# HC05_shield.net
KiCad netlist of a schematic drawn in EAGLE
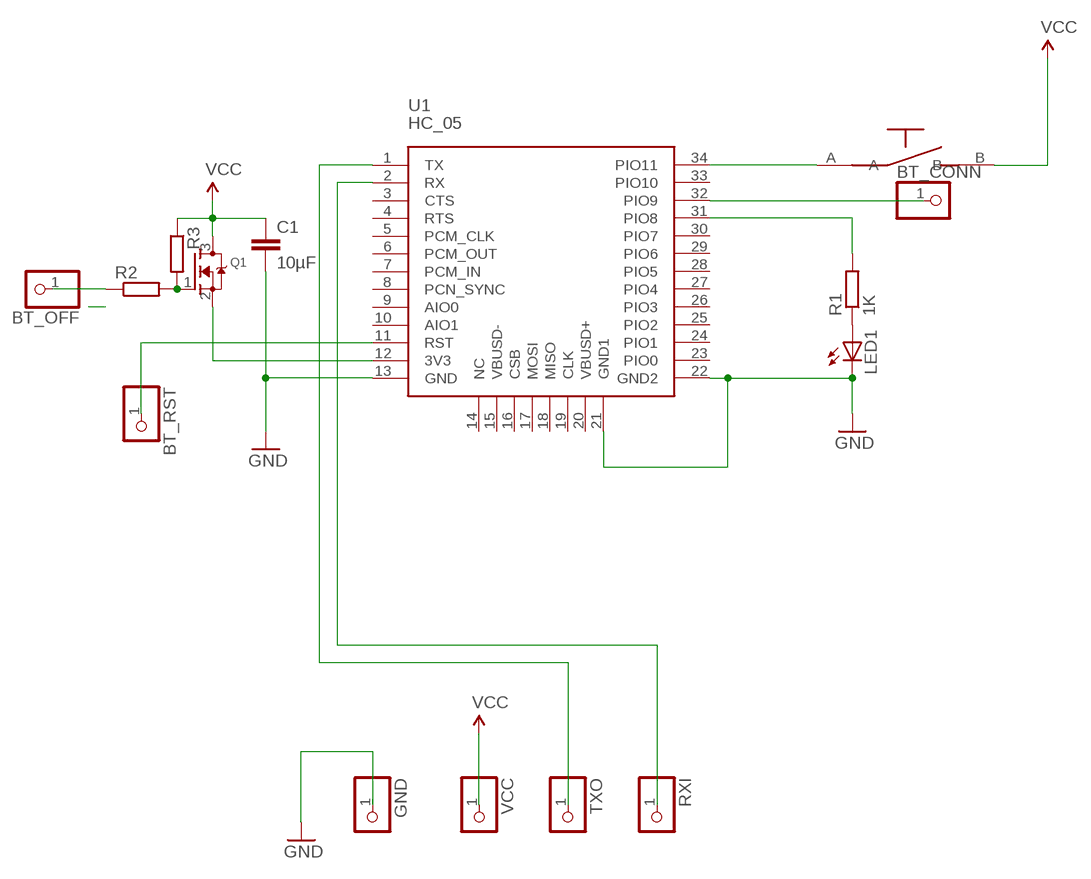
[diagram p0: schematic, sheet 1]

(export (version "E")
  (design (tool "Eeschema 10.0.6"))
  (components
    (comp (ref "BT_CONN")
      (value "PINHD-1X1")
      (footprint "eagle-import:1X01")
      (libsource (lib "eagle-import") (part "PINHD-1X1"))
    )
    (comp (ref "BT_OFF")
      (value "PINHD-1X1")
      (footprint "eagle-import:1X01")
      (libsource (lib "eagle-import") (part "PINHD-1X1"))
    )
    (comp (ref "BT_RST")
      (value "PINHD-1X1")
      (footprint "eagle-import:1X01")
      (libsource (lib "eagle-import") (part "PINHD-1X1"))
    )
    (comp (ref "C1")
      (value "10µF")
      (footprint "eagle-import:C0805")
      (libsource (lib "eagle-import") (part "C-EUC0805"))
    )
    (comp (ref "GND")
      (value "PINHD-1X1")
      (footprint "eagle-import:1X01")
      (libsource (lib "eagle-import") (part "PINHD-1X1"))
    )
    (comp (ref "LED1")
      (value "LEDCHIP-LED0805")
      (footprint "eagle-import:CHIP-LED0805")
      (libsource (lib "eagle-import") (part "LEDCHIP-LED0805"))
    )
    (comp (ref "Q1")
      (value "MOSFET-NREFLOW")
      (footprint "eagle-import:SOT23")
      (libsource (lib "eagle-import") (part "MOSFET-NREFLOW"))
    )
    (comp (ref "R1")
      (value "1K")
      (footprint "eagle-import:R0805")
      (libsource (lib "eagle-import") (part "R-EU_R0805"))
    )
    (comp (ref "R2")
      (value "R-EU_R0603")
      (footprint "eagle-import:R0603")
      (libsource (lib "eagle-import") (part "R-EU_R0603"))
    )
    (comp (ref "R3")
      (value "R-EU_R0603")
      (footprint "eagle-import:R0603")
      (libsource (lib "eagle-import") (part "R-EU_R0603"))
    )
    (comp (ref "RXI")
      (value "PINHD-1X1")
      (footprint "eagle-import:1X01")
      (libsource (lib "eagle-import") (part "PINHD-1X1"))
    )
    (comp (ref "TXO")
      (value "PINHD-1X1")
      (footprint "eagle-import:1X01")
      (libsource (lib "eagle-import") (part "PINHD-1X1"))
    )
    (comp (ref "U$2")
      (value "SWITCH2PIN")
      (footprint "eagle-import:SWITCH2PIN")
      (libsource (lib "eagle-import") (part "SWITCH2PIN"))
    )
    (comp (ref "U1")
      (value "HC_05")
      (footprint "eagle-import:BLUETOOTH_SMD")
      (libsource (lib "eagle-import") (part "HC_05"))
    )
    (comp (ref "VCC")
      (value "PINHD-1X1")
      (footprint "eagle-import:1X01")
      (libsource (lib "eagle-import") (part "PINHD-1X1"))
    )
  )
  (nets
    (net (code "1") (name "/N$11") (class "Default")
      (node (ref "BT_OFF") (pin "1") (pinfunction "1_1") (pintype "passive"))
      (node (ref "R2") (pin "1") (pinfunction "1_1") (pintype "passive"))
    )
    (net (code "2") (name "GND") (class "Default")
      (node (ref "C1") (pin "2") (pinfunction "2_2") (pintype "passive"))
      (node (ref "GND") (pin "1") (pinfunction "1_1") (pintype "passive"))
      (node (ref "LED1") (pin "C") (pinfunction "C_C") (pintype "passive"))
      (node (ref "U1") (pin "13") (pinfunction "GND_13") (pintype "bidirectional"))
      (node (ref "U1") (pin "21") (pinfunction "GND1_21") (pintype "bidirectional"))
      (node (ref "U1") (pin "22") (pinfunction "GND2_22") (pintype "bidirectional"))
    )
    (net (code "3") (name "Net-(LED1-PadA)") (class "Default")
      (node (ref "LED1") (pin "A") (pinfunction "A_A") (pintype "passive"))
      (node (ref "R1") (pin "1") (pinfunction "1_1") (pintype "passive"))
    )
    (net (code "4") (name "Net-(Q1-G)") (class "Default")
      (node (ref "Q1") (pin "1") (pinfunction "G_1") (pintype "bidirectional"))
      (node (ref "R2") (pin "2") (pinfunction "2_2") (pintype "passive"))
      (node (ref "R3") (pin "2") (pinfunction "2_2") (pintype "passive"))
    )
    (net (code "5") (name "Net-(Q1-S)") (class "Default")
      (node (ref "Q1") (pin "2") (pinfunction "S_2") (pintype "bidirectional"))
      (node (ref "U1") (pin "12") (pinfunction "3V3_12") (pintype "bidirectional"))
    )
    (net (code "6") (name "Net-(U1-PIO8)") (class "Default")
      (node (ref "R1") (pin "2") (pinfunction "2_2") (pintype "passive"))
      (node (ref "U1") (pin "31") (pinfunction "PIO8_31") (pintype "bidirectional"))
    )
    (net (code "7") (name "Net-(U1-PIO9)") (class "Default")
      (node (ref "BT_CONN") (pin "1") (pinfunction "1_1") (pintype "passive"))
      (node (ref "U1") (pin "32") (pinfunction "PIO9_32") (pintype "bidirectional"))
    )
    (net (code "8") (name "Net-(U1-PIO11)") (class "Default")
      (node (ref "U$2") (pin "A") (pinfunction "A_A") (pintype "bidirectional"))
      (node (ref "U1") (pin "34") (pinfunction "PIO11_34") (pintype "bidirectional"))
    )
    (net (code "9") (name "Net-(U1-RST)") (class "Default")
      (node (ref "BT_RST") (pin "1") (pinfunction "1_1") (pintype "passive"))
      (node (ref "U1") (pin "11") (pinfunction "RST_11") (pintype "bidirectional"))
    )
    (net (code "10") (name "Net-(U1-RX)") (class "Default")
      (node (ref "RXI") (pin "1") (pinfunction "1_1") (pintype "passive"))
      (node (ref "U1") (pin "2") (pinfunction "RX_2") (pintype "bidirectional"))
    )
    (net (code "11") (name "Net-(U1-TX)") (class "Default")
      (node (ref "TXO") (pin "1") (pinfunction "1_1") (pintype "passive"))
      (node (ref "U1") (pin "1") (pinfunction "TX_1") (pintype "bidirectional"))
    )
    (net (code "12") (name "VCC") (class "Default")
      (node (ref "C1") (pin "1") (pinfunction "1_1") (pintype "passive"))
      (node (ref "Q1") (pin "3") (pinfunction "D_3") (pintype "bidirectional"))
      (node (ref "R3") (pin "1") (pinfunction "1_1") (pintype "passive"))
      (node (ref "U$2") (pin "B") (pinfunction "B_B") (pintype "bidirectional"))
      (node (ref "VCC") (pin "1") (pinfunction "1_1") (pintype "passive"))
    )
    (net (code "13") (name "unconnected-(U1-AIO0-Pad9)") (class "Default")
      (node (ref "U1") (pin "9") (pinfunction "AIO0_9") (pintype "bidirectional"))
    )
    (net (code "14") (name "unconnected-(U1-AIO1-Pad10)") (class "Default")
      (node (ref "U1") (pin "10") (pinfunction "AIO1_10") (pintype "bidirectional"))
    )
    (net (code "15") (name "unconnected-(U1-CLK-Pad19)") (class "Default")
      (node (ref "U1") (pin "19") (pinfunction "CLK_19") (pintype "bidirectional"))
    )
    (net (code "16") (name "unconnected-(U1-CSB-Pad16)") (class "Default")
      (node (ref "U1") (pin "16") (pinfunction "CSB_16") (pintype "bidirectional"))
    )
    (net (code "17") (name "unconnected-(U1-CTS-Pad3)") (class "Default")
      (node (ref "U1") (pin "3") (pinfunction "CTS_3") (pintype "bidirectional"))
    )
    (net (code "18") (name "unconnected-(U1-MISO-Pad18)") (class "Default")
      (node (ref "U1") (pin "18") (pinfunction "MISO_18") (pintype "bidirectional"))
    )
    (net (code "19") (name "unconnected-(U1-MOSI-Pad17)") (class "Default")
      (node (ref "U1") (pin "17") (pinfunction "MOSI_17") (pintype "bidirectional"))
    )
    (net (code "20") (name "unconnected-(U1-NC-Pad14)") (class "Default")
      (node (ref "U1") (pin "14") (pinfunction "NC_14") (pintype "bidirectional"))
    )
    (net (code "21") (name "unconnected-(U1-PCM_CLK-Pad5)") (class "Default")
      (node (ref "U1") (pin "5") (pinfunction "PCM_CLK_5") (pintype "bidirectional"))
    )
    (net (code "22") (name "unconnected-(U1-PCM_IN-Pad7)") (class "Default")
      (node (ref "U1") (pin "7") (pinfunction "PCM_IN_7") (pintype "bidirectional"))
    )
    (net (code "23") (name "unconnected-(U1-PCM_OUT-Pad6)") (class "Default")
      (node (ref "U1") (pin "6") (pinfunction "PCM_OUT_6") (pintype "bidirectional"))
    )
    (net (code "24") (name "unconnected-(U1-PCN_SYNC-Pad8)") (class "Default")
      (node (ref "U1") (pin "8") (pinfunction "PCN_SYNC_8") (pintype "bidirectional"))
    )
    (net (code "25") (name "unconnected-(U1-PIO0-Pad23)") (class "Default")
      (node (ref "U1") (pin "23") (pinfunction "PIO0_23") (pintype "bidirectional"))
    )
    (net (code "26") (name "unconnected-(U1-PIO1-Pad24)") (class "Default")
      (node (ref "U1") (pin "24") (pinfunction "PIO1_24") (pintype "bidirectional"))
    )
    (net (code "27") (name "unconnected-(U1-PIO2-Pad25)") (class "Default")
      (node (ref "U1") (pin "25") (pinfunction "PIO2_25") (pintype "bidirectional"))
    )
    (net (code "28") (name "unconnected-(U1-PIO3-Pad26)") (class "Default")
      (node (ref "U1") (pin "26") (pinfunction "PIO3_26") (pintype "bidirectional"))
    )
    (net (code "29") (name "unconnected-(U1-PIO4-Pad27)") (class "Default")
      (node (ref "U1") (pin "27") (pinfunction "PIO4_27") (pintype "bidirectional"))
    )
    (net (code "30") (name "unconnected-(U1-PIO5-Pad28)") (class "Default")
      (node (ref "U1") (pin "28") (pinfunction "PIO5_28") (pintype "bidirectional"))
    )
    (net (code "31") (name "unconnected-(U1-PIO6-Pad29)") (class "Default")
      (node (ref "U1") (pin "29") (pinfunction "PIO6_29") (pintype "bidirectional"))
    )
    (net (code "32") (name "unconnected-(U1-PIO7-Pad30)") (class "Default")
      (node (ref "U1") (pin "30") (pinfunction "PIO7_30") (pintype "bidirectional"))
    )
    (net (code "33") (name "unconnected-(U1-PIO10-Pad33)") (class "Default")
      (node (ref "U1") (pin "33") (pinfunction "PIO10_33") (pintype "bidirectional"))
    )
    (net (code "34") (name "unconnected-(U1-RTS-Pad4)") (class "Default")
      (node (ref "U1") (pin "4") (pinfunction "RTS_4") (pintype "bidirectional"))
    )
    (net (code "35") (name "unconnected-(U1-VBUSD+-Pad20)") (class "Default")
      (node (ref "U1") (pin "20") (pinfunction "VBUSD+_20") (pintype "bidirectional"))
    )
    (net (code "36") (name "unconnected-(U1-VBUSD--Pad15)") (class "Default")
      (node (ref "U1") (pin "15") (pinfunction "VBUSD-_15") (pintype "bidirectional"))
    )
  )
)
